# IMX7S_CPU_POWER.net
KiCad netlist of a schematic drawn in Altium Designer
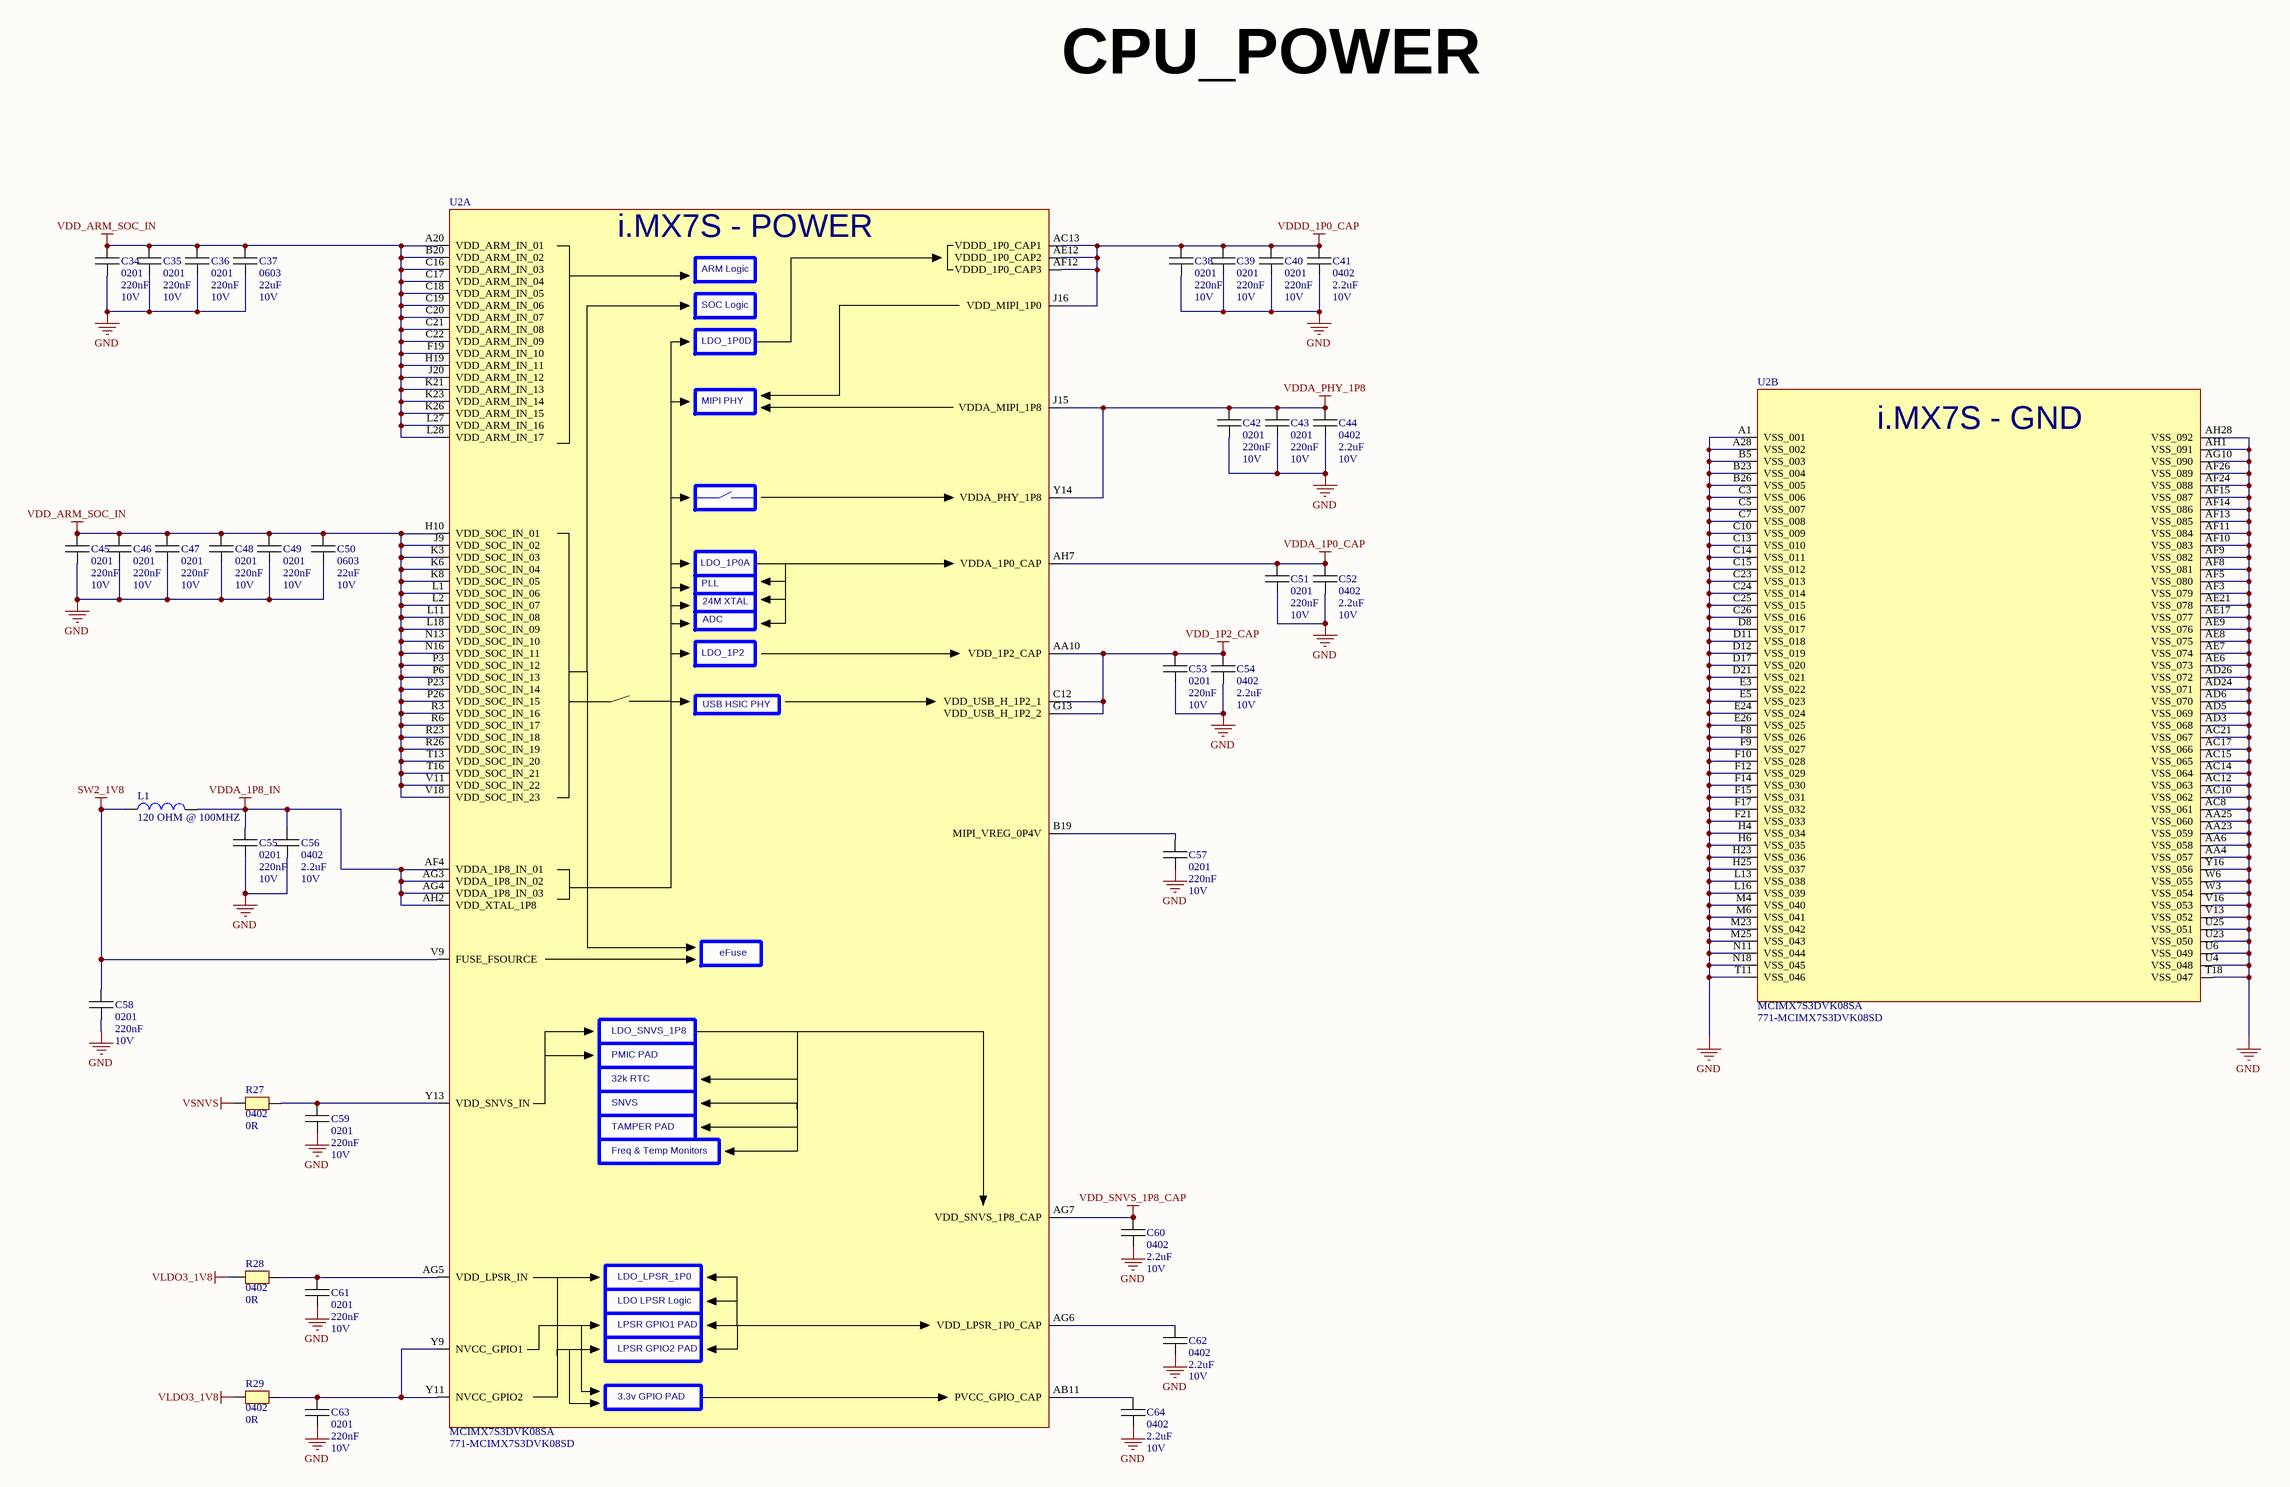
[diagram p0: IMX7S_CPU_POWER.SchDoc]

(export (version "E")
  (design (tool "Eeschema 10.0.6"))
  (components
    (comp (ref "C34")
      (value "220nF")
      (footprint "C0201")
      (fields
        (field (name "PACKAGE") "0201")
        (field (name "VOLTAGE") "10V")
        (field (name "TOLERANCE") "10%")
        (field (name "Comment") "C0201")
      )
      (libsource (lib "Schlib_IMX7") (part "C0201"))
    )
    (comp (ref "C35")
      (value "220nF")
      (footprint "C0201")
      (fields
        (field (name "PACKAGE") "0201")
        (field (name "VOLTAGE") "10V")
        (field (name "TOLERANCE") "10%")
        (field (name "Comment") "C0201")
      )
      (libsource (lib "Schlib_IMX7") (part "C0201"))
    )
    (comp (ref "C36")
      (value "220nF")
      (footprint "C0201")
      (fields
        (field (name "PACKAGE") "0201")
        (field (name "VOLTAGE") "10V")
        (field (name "TOLERANCE") "10%")
        (field (name "Comment") "C0201")
      )
      (libsource (lib "Schlib_IMX7") (part "C0201"))
    )
    (comp (ref "C37")
      (value "22uF")
      (footprint "C0603")
      (description "Cap Ceramic 22uF 6.3V X5R 20% SMD 0603 85C Paper T/R")
      (fields
        (field (name "PACKAGE") "0603")
        (field (name "VOLTAGE") "10V")
        (field (name "TOLERANCE") "20%")
        (field (name "Comment") "C0603")
      )
      (libsource (lib "Schlib_IMX7") (part "C0603"))
    )
    (comp (ref "C38")
      (value "220nF")
      (footprint "C0201")
      (fields
        (field (name "PACKAGE") "0201")
        (field (name "VOLTAGE") "10V")
        (field (name "TOLERANCE") "10%")
        (field (name "Comment") "C0201")
      )
      (libsource (lib "Schlib_IMX7") (part "C0201"))
    )
    (comp (ref "C39")
      (value "220nF")
      (footprint "C0201")
      (fields
        (field (name "PACKAGE") "0201")
        (field (name "VOLTAGE") "10V")
        (field (name "TOLERANCE") "10%")
        (field (name "Comment") "C0201")
      )
      (libsource (lib "Schlib_IMX7") (part "C0201"))
    )
    (comp (ref "C40")
      (value "220nF")
      (footprint "C0201")
      (fields
        (field (name "PACKAGE") "0201")
        (field (name "VOLTAGE") "10V")
        (field (name "TOLERANCE") "10%")
        (field (name "Comment") "C0201")
      )
      (libsource (lib "Schlib_IMX7") (part "C0201"))
    )
    (comp (ref "C41")
      (value "2.2uF")
      (footprint "C0402")
      (fields
        (field (name "PACKAGE") "0402")
        (field (name "VOLTAGE") "10V")
        (field (name "TOLERANCE") "20%")
        (field (name "Comment") "C0402")
      )
      (libsource (lib "Schlib_IMX7") (part "C0402"))
    )
    (comp (ref "C42")
      (value "220nF")
      (footprint "C0201")
      (fields
        (field (name "PACKAGE") "0201")
        (field (name "VOLTAGE") "10V")
        (field (name "TOLERANCE") "10%")
        (field (name "Comment") "C0201")
      )
      (libsource (lib "Schlib_IMX7") (part "C0201"))
    )
    (comp (ref "C43")
      (value "220nF")
      (footprint "C0201")
      (fields
        (field (name "PACKAGE") "0201")
        (field (name "VOLTAGE") "10V")
        (field (name "TOLERANCE") "10%")
        (field (name "Comment") "C0201")
      )
      (libsource (lib "Schlib_IMX7") (part "C0201"))
    )
    (comp (ref "C44")
      (value "2.2uF")
      (footprint "C0402")
      (fields
        (field (name "PACKAGE") "0402")
        (field (name "VOLTAGE") "10V")
        (field (name "TOLERANCE") "20%")
        (field (name "Comment") "C0402")
      )
      (libsource (lib "Schlib_IMX7") (part "C0402"))
    )
    (comp (ref "C45")
      (value "220nF")
      (footprint "C0201")
      (fields
        (field (name "PACKAGE") "0201")
        (field (name "VOLTAGE") "10V")
        (field (name "TOLERANCE") "10%")
        (field (name "Comment") "C0201")
      )
      (libsource (lib "Schlib_IMX7") (part "C0201"))
    )
    (comp (ref "C46")
      (value "220nF")
      (footprint "C0201")
      (fields
        (field (name "PACKAGE") "0201")
        (field (name "VOLTAGE") "10V")
        (field (name "TOLERANCE") "10%")
        (field (name "Comment") "C0201")
      )
      (libsource (lib "Schlib_IMX7") (part "C0201"))
    )
    (comp (ref "C47")
      (value "220nF")
      (footprint "C0201")
      (fields
        (field (name "PACKAGE") "0201")
        (field (name "VOLTAGE") "10V")
        (field (name "TOLERANCE") "10%")
        (field (name "Comment") "C0201")
      )
      (libsource (lib "Schlib_IMX7") (part "C0201"))
    )
    (comp (ref "C48")
      (value "220nF")
      (footprint "C0201")
      (fields
        (field (name "PACKAGE") "0201")
        (field (name "VOLTAGE") "10V")
        (field (name "TOLERANCE") "10%")
        (field (name "Comment") "C0201")
      )
      (libsource (lib "Schlib_IMX7") (part "C0201"))
    )
    (comp (ref "C49")
      (value "220nF")
      (footprint "C0201")
      (fields
        (field (name "PACKAGE") "0201")
        (field (name "VOLTAGE") "10V")
        (field (name "TOLERANCE") "10%")
        (field (name "Comment") "C0201")
      )
      (libsource (lib "Schlib_IMX7") (part "C0201"))
    )
    (comp (ref "C50")
      (value "22uF")
      (footprint "C0603")
      (description "Cap Ceramic 22uF 6.3V X5R 20% SMD 0603 85C Paper T/R")
      (fields
        (field (name "PACKAGE") "0603")
        (field (name "VOLTAGE") "10V")
        (field (name "TOLERANCE") "20%")
        (field (name "Comment") "C0603")
      )
      (libsource (lib "Schlib_IMX7") (part "C0603"))
    )
    (comp (ref "C51")
      (value "220nF")
      (footprint "C0201")
      (fields
        (field (name "PACKAGE") "0201")
        (field (name "VOLTAGE") "10V")
        (field (name "TOLERANCE") "10%")
        (field (name "Comment") "C0201")
      )
      (libsource (lib "Schlib_IMX7") (part "C0201"))
    )
    (comp (ref "C52")
      (value "2.2uF")
      (footprint "C0402")
      (fields
        (field (name "PACKAGE") "0402")
        (field (name "VOLTAGE") "10V")
        (field (name "TOLERANCE") "20%")
        (field (name "Comment") "C0402")
      )
      (libsource (lib "Schlib_IMX7") (part "C0402"))
    )
    (comp (ref "C53")
      (value "220nF")
      (footprint "C0201")
      (fields
        (field (name "PACKAGE") "0201")
        (field (name "VOLTAGE") "10V")
        (field (name "TOLERANCE") "10%")
        (field (name "Comment") "C0201")
      )
      (libsource (lib "Schlib_IMX7") (part "C0201"))
    )
    (comp (ref "C54")
      (value "2.2uF")
      (footprint "C0402")
      (fields
        (field (name "PACKAGE") "0402")
        (field (name "VOLTAGE") "10V")
        (field (name "TOLERANCE") "20%")
        (field (name "Comment") "C0402")
      )
      (libsource (lib "Schlib_IMX7") (part "C0402"))
    )
    (comp (ref "C55")
      (value "220nF")
      (footprint "C0201")
      (fields
        (field (name "PACKAGE") "0201")
        (field (name "VOLTAGE") "10V")
        (field (name "TOLERANCE") "10%")
        (field (name "Comment") "C0201")
      )
      (libsource (lib "Schlib_IMX7") (part "C0201"))
    )
    (comp (ref "C56")
      (value "2.2uF")
      (footprint "C0402")
      (fields
        (field (name "PACKAGE") "0402")
        (field (name "VOLTAGE") "10V")
        (field (name "TOLERANCE") "20%")
        (field (name "Comment") "C0402")
      )
      (libsource (lib "Schlib_IMX7") (part "C0402"))
    )
    (comp (ref "C57")
      (value "220nF")
      (footprint "C0201")
      (fields
        (field (name "PACKAGE") "0201")
        (field (name "VOLTAGE") "10V")
        (field (name "TOLERANCE") "10%")
        (field (name "Comment") "C0201")
      )
      (libsource (lib "Schlib_IMX7") (part "C0201"))
    )
    (comp (ref "C58")
      (value "220nF")
      (footprint "C0201")
      (fields
        (field (name "PACKAGE") "0201")
        (field (name "VOLTAGE") "10V")
        (field (name "TOLERANCE") "10%")
        (field (name "Comment") "C0201")
      )
      (libsource (lib "Schlib_IMX7") (part "C0201"))
    )
    (comp (ref "C59")
      (value "220nF")
      (footprint "C0201")
      (fields
        (field (name "PACKAGE") "0201")
        (field (name "VOLTAGE") "10V")
        (field (name "TOLERANCE") "10%")
        (field (name "Comment") "C0201")
      )
      (libsource (lib "Schlib_IMX7") (part "C0201"))
    )
    (comp (ref "C60")
      (value "2.2uF")
      (footprint "C0402")
      (fields
        (field (name "PACKAGE") "0402")
        (field (name "VOLTAGE") "10V")
        (field (name "TOLERANCE") "20%")
        (field (name "Comment") "C0402")
      )
      (libsource (lib "Schlib_IMX7") (part "C0402"))
    )
    (comp (ref "C61")
      (value "220nF")
      (footprint "C0201")
      (fields
        (field (name "PACKAGE") "0201")
        (field (name "VOLTAGE") "10V")
        (field (name "TOLERANCE") "10%")
        (field (name "Comment") "C0201")
      )
      (libsource (lib "Schlib_IMX7") (part "C0201"))
    )
    (comp (ref "C62")
      (value "2.2uF")
      (footprint "C0402")
      (fields
        (field (name "PACKAGE") "0402")
        (field (name "VOLTAGE") "10V")
        (field (name "TOLERANCE") "20%")
        (field (name "Comment") "C0402")
      )
      (libsource (lib "Schlib_IMX7") (part "C0402"))
    )
    (comp (ref "C63")
      (value "220nF")
      (footprint "C0201")
      (fields
        (field (name "PACKAGE") "0201")
        (field (name "VOLTAGE") "10V")
        (field (name "TOLERANCE") "10%")
        (field (name "Comment") "C0201")
      )
      (libsource (lib "Schlib_IMX7") (part "C0201"))
    )
    (comp (ref "C64")
      (value "2.2uF")
      (footprint "C0402")
      (fields
        (field (name "PACKAGE") "0402")
        (field (name "VOLTAGE") "10V")
        (field (name "TOLERANCE") "20%")
        (field (name "Comment") "C0402")
      )
      (libsource (lib "Schlib_IMX7") (part "C0402"))
    )
    (comp (ref "L1")
      (value "120 OHM @ 100MHZ")
      (footprint "SELF")
      (description "10mH Unshielded Wirewound Inductor 35mA 120 Ohm Max 2220 (5750 Metric)")
      (fields (field (name "TOLERANCE") "10%") (field (name "Comment") "Self"))
      (libsource (lib "Schlib_IMX7") (part "Self"))
    )
    (comp (ref "R27")
      (value "0R")
      (footprint "R0402")
      (description "MULTICOMP - MCSR04X000 PTL - RES, 0R0, 0.0625W, 0402, CERAMIC")
      (fields (field (name "PACKAGE") "0402") (field (name "VOLTAGE") "0V") (field (name "Comment") "R0402"))
      (libsource (lib "Schlib_IMX7") (part "R0402"))
    )
    (comp (ref "R28")
      (value "0R")
      (footprint "R0402")
      (description "MULTICOMP - MCSR04X000 PTL - RES, 0R0, 0.0625W, 0402, CERAMIC")
      (fields (field (name "PACKAGE") "0402") (field (name "VOLTAGE") "0V") (field (name "Comment") "R0402"))
      (libsource (lib "Schlib_IMX7") (part "R0402"))
    )
    (comp (ref "R29")
      (value "0R")
      (footprint "R0402")
      (description "MULTICOMP - MCSR04X000 PTL - RES, 0R0, 0.0625W, 0402, CERAMIC")
      (fields (field (name "PACKAGE") "0402") (field (name "VOLTAGE") "0V") (field (name "Comment") "R0402"))
      (libsource (lib "Schlib_IMX7") (part "R0402"))
    )
    (comp (ref "U2")
      (value "MCIMX7S3DVK08SA")
      (footprint "BGA 488 PIN")
      (fields (field (name "SUPPLIER PART NUMBER 1") "771-MCIMX7S3DVK08SD"))
      (libsource (lib "Schlib_IMX7") (part "MCIMX7S3DVK08SD"))
    )
  )
  (nets
    (net (code "1") (name "GND") (class "Default")
      (node (ref "C34") (pin "1") (pinfunction "1_1") (pintype "passive"))
      (node (ref "C35") (pin "1") (pinfunction "1_1") (pintype "passive"))
      (node (ref "C36") (pin "1") (pinfunction "1_1") (pintype "passive"))
      (node (ref "C37") (pin "1") (pinfunction "1_1") (pintype "passive"))
      (node (ref "C38") (pin "1") (pinfunction "1_1") (pintype "passive"))
      (node (ref "C39") (pin "1") (pinfunction "1_1") (pintype "passive"))
      (node (ref "C40") (pin "1") (pinfunction "1_1") (pintype "passive"))
      (node (ref "C41") (pin "1") (pinfunction "1_1") (pintype "passive"))
      (node (ref "C42") (pin "1") (pinfunction "1_1") (pintype "passive"))
      (node (ref "C43") (pin "1") (pinfunction "1_1") (pintype "passive"))
      (node (ref "C44") (pin "1") (pinfunction "1_1") (pintype "passive"))
      (node (ref "C45") (pin "1") (pinfunction "1_1") (pintype "passive"))
      (node (ref "C46") (pin "1") (pinfunction "1_1") (pintype "passive"))
      (node (ref "C47") (pin "1") (pinfunction "1_1") (pintype "passive"))
      (node (ref "C48") (pin "1") (pinfunction "1_1") (pintype "passive"))
      (node (ref "C49") (pin "1") (pinfunction "1_1") (pintype "passive"))
      (node (ref "C50") (pin "1") (pinfunction "1_1") (pintype "passive"))
      (node (ref "C51") (pin "1") (pinfunction "1_1") (pintype "passive"))
      (node (ref "C52") (pin "1") (pinfunction "1_1") (pintype "passive"))
      (node (ref "C53") (pin "1") (pinfunction "1_1") (pintype "passive"))
      (node (ref "C54") (pin "1") (pinfunction "1_1") (pintype "passive"))
      (node (ref "C55") (pin "1") (pinfunction "1_1") (pintype "passive"))
      (node (ref "C56") (pin "1") (pinfunction "1_1") (pintype "passive"))
      (node (ref "C57") (pin "1") (pinfunction "1_1") (pintype "passive"))
      (node (ref "C58") (pin "1") (pinfunction "1_1") (pintype "passive"))
      (node (ref "C59") (pin "1") (pinfunction "1_1") (pintype "passive"))
      (node (ref "C60") (pin "1") (pinfunction "1_1") (pintype "passive"))
      (node (ref "C61") (pin "1") (pinfunction "1_1") (pintype "passive"))
      (node (ref "C62") (pin "1") (pinfunction "1_1") (pintype "passive"))
      (node (ref "C63") (pin "1") (pinfunction "1_1") (pintype "passive"))
      (node (ref "C64") (pin "1") (pinfunction "1_1") (pintype "passive"))
      (node (ref "U2") (pin "A1") (pinfunction "VSS_001_A1") (pintype "passive"))
      (node (ref "U2") (pin "A28") (pinfunction "VSS_002_A28") (pintype "passive"))
      (node (ref "U2") (pin "AA23") (pinfunction "VSS_059_AA23") (pintype "passive"))
      (node (ref "U2") (pin "AA25") (pinfunction "VSS_060_AA25") (pintype "passive"))
      (node (ref "U2") (pin "AA4") (pinfunction "VSS_057_AA4") (pintype "passive"))
      (node (ref "U2") (pin "AA6") (pinfunction "VSS_058_AA6") (pintype "passive"))
      (node (ref "U2") (pin "AC10") (pinfunction "VSS_062_AC10") (pintype "passive"))
      (node (ref "U2") (pin "AC12") (pinfunction "VSS_063_AC12") (pintype "passive"))
      (node (ref "U2") (pin "AC14") (pinfunction "VSS_064_AC14") (pintype "passive"))
      (node (ref "U2") (pin "AC15") (pinfunction "VSS_065_AC15") (pintype "passive"))
      (node (ref "U2") (pin "AC17") (pinfunction "VSS_066_AC17") (pintype "passive"))
      (node (ref "U2") (pin "AC21") (pinfunction "VSS_067_AC21") (pintype "passive"))
      (node (ref "U2") (pin "AC8") (pinfunction "VSS_061_AC8") (pintype "passive"))
      (node (ref "U2") (pin "AD24") (pinfunction "VSS_071_AD24") (pintype "passive"))
      (node (ref "U2") (pin "AD26") (pinfunction "VSS_072_AD26") (pintype "passive"))
      (node (ref "U2") (pin "AD3") (pinfunction "VSS_068_AD3") (pintype "passive"))
      (node (ref "U2") (pin "AD5") (pinfunction "VSS_069_AD5") (pintype "passive"))
      (node (ref "U2") (pin "AD6") (pinfunction "VSS_070_AD6") (pintype "passive"))
      (node (ref "U2") (pin "AE17") (pinfunction "VSS_077_AE17") (pintype "passive"))
      (node (ref "U2") (pin "AE21") (pinfunction "VSS_078_AE21") (pintype "passive"))
      (node (ref "U2") (pin "AE6") (pinfunction "VSS_073_AE6") (pintype "passive"))
      (node (ref "U2") (pin "AE7") (pinfunction "VSS_074_AE7") (pintype "passive"))
      (node (ref "U2") (pin "AE8") (pinfunction "VSS_075_AE8") (pintype "passive"))
      (node (ref "U2") (pin "AE9") (pinfunction "VSS_076_AE9") (pintype "passive"))
      (node (ref "U2") (pin "AF10") (pinfunction "VSS_083_AF10") (pintype "passive"))
      (node (ref "U2") (pin "AF11") (pinfunction "VSS_084_AF11") (pintype "passive"))
      (node (ref "U2") (pin "AF13") (pinfunction "VSS_085_AF13") (pintype "passive"))
      (node (ref "U2") (pin "AF14") (pinfunction "VSS_086_AF14") (pintype "passive"))
      (node (ref "U2") (pin "AF15") (pinfunction "VSS_087_AF15") (pintype "passive"))
      (node (ref "U2") (pin "AF24") (pinfunction "VSS_088_AF24") (pintype "passive"))
      (node (ref "U2") (pin "AF26") (pinfunction "VSS_089_AF26") (pintype "passive"))
      (node (ref "U2") (pin "AF3") (pinfunction "VSS_079_AF3") (pintype "passive"))
      (node (ref "U2") (pin "AF5") (pinfunction "VSS_080_AF5") (pintype "passive"))
      (node (ref "U2") (pin "AF8") (pinfunction "VSS_081_AF8") (pintype "passive"))
      (node (ref "U2") (pin "AF9") (pinfunction "VSS_082_AF9") (pintype "passive"))
      (node (ref "U2") (pin "AG10") (pinfunction "VSS_090_AG10") (pintype "passive"))
      (node (ref "U2") (pin "AH1") (pinfunction "VSS_091_AH1") (pintype "passive"))
      (node (ref "U2") (pin "AH28") (pinfunction "VSS_092_AH28") (pintype "passive"))
      (node (ref "U2") (pin "B23") (pinfunction "VSS_004_B23") (pintype "passive"))
      (node (ref "U2") (pin "B26") (pinfunction "VSS_005_B26") (pintype "passive"))
      (node (ref "U2") (pin "B5") (pinfunction "VSS_003_B5") (pintype "passive"))
      (node (ref "U2") (pin "C10") (pinfunction "VSS_009_C10") (pintype "passive"))
      (node (ref "U2") (pin "C13") (pinfunction "VSS_010_C13") (pintype "passive"))
      (node (ref "U2") (pin "C14") (pinfunction "VSS_011_C14") (pintype "passive"))
      (node (ref "U2") (pin "C15") (pinfunction "VSS_012_C15") (pintype "passive"))
      (node (ref "U2") (pin "C23") (pinfunction "VSS_013_C23") (pintype "passive"))
      (node (ref "U2") (pin "C24") (pinfunction "VSS_014_C24") (pintype "passive"))
      (node (ref "U2") (pin "C25") (pinfunction "VSS_015_C25") (pintype "passive"))
      (node (ref "U2") (pin "C26") (pinfunction "VSS_016_C26") (pintype "passive"))
      (node (ref "U2") (pin "C3") (pinfunction "VSS_006_C3") (pintype "passive"))
      (node (ref "U2") (pin "C5") (pinfunction "VSS_007_C5") (pintype "passive"))
      (node (ref "U2") (pin "C7") (pinfunction "VSS_008_C7") (pintype "passive"))
      (node (ref "U2") (pin "D11") (pinfunction "VSS_018_D11") (pintype "passive"))
      (node (ref "U2") (pin "D12") (pinfunction "VSS_019_D12") (pintype "passive"))
      (node (ref "U2") (pin "D17") (pinfunction "VSS_020_D17") (pintype "passive"))
      (node (ref "U2") (pin "D21") (pinfunction "VSS_021_D21") (pintype "passive"))
      (node (ref "U2") (pin "D8") (pinfunction "VSS_017_D8") (pintype "passive"))
      (node (ref "U2") (pin "E24") (pinfunction "VSS_024_E24") (pintype "passive"))
      (node (ref "U2") (pin "E26") (pinfunction "VSS_025_E26") (pintype "passive"))
      (node (ref "U2") (pin "E3") (pinfunction "VSS_022_E3") (pintype "passive"))
      (node (ref "U2") (pin "E5") (pinfunction "VSS_023_E5") (pintype "passive"))
      (node (ref "U2") (pin "F10") (pinfunction "VSS_028_F10") (pintype "passive"))
      (node (ref "U2") (pin "F12") (pinfunction "VSS_029_F12") (pintype "passive"))
      (node (ref "U2") (pin "F14") (pinfunction "VSS_030_F14") (pintype "passive"))
      (node (ref "U2") (pin "F15") (pinfunction "VSS_031_F15") (pintype "passive"))
      (node (ref "U2") (pin "F17") (pinfunction "VSS_032_F17") (pintype "passive"))
      (node (ref "U2") (pin "F21") (pinfunction "VSS_033_F21") (pintype "passive"))
      (node (ref "U2") (pin "F8") (pinfunction "VSS_026_F8") (pintype "passive"))
      (node (ref "U2") (pin "F9") (pinfunction "VSS_027_F9") (pintype "passive"))
      (node (ref "U2") (pin "H23") (pinfunction "VSS_036_H23") (pintype "passive"))
      (node (ref "U2") (pin "H25") (pinfunction "VSS_037_H25") (pintype "passive"))
      (node (ref "U2") (pin "H4") (pinfunction "VSS_034_H4") (pintype "passive"))
      (node (ref "U2") (pin "H6") (pinfunction "VSS_035_H6") (pintype "passive"))
      (node (ref "U2") (pin "L13") (pinfunction "VSS_038_L13") (pintype "passive"))
      (node (ref "U2") (pin "L16") (pinfunction "VSS_039_L16") (pintype "passive"))
      (node (ref "U2") (pin "M23") (pinfunction "VSS_042_M23") (pintype "passive"))
      (node (ref "U2") (pin "M25") (pinfunction "VSS_043_M25") (pintype "passive"))
      (node (ref "U2") (pin "M4") (pinfunction "VSS_040_M4") (pintype "passive"))
      (node (ref "U2") (pin "M6") (pinfunction "VSS_041_M6") (pintype "passive"))
      (node (ref "U2") (pin "N11") (pinfunction "VSS_044_N11") (pintype "passive"))
      (node (ref "U2") (pin "N18") (pinfunction "VSS_045_N18") (pintype "passive"))
      (node (ref "U2") (pin "T11") (pinfunction "VSS_046_T11") (pintype "passive"))
      (node (ref "U2") (pin "T18") (pinfunction "VSS_047_T18") (pintype "passive"))
      (node (ref "U2") (pin "U23") (pinfunction "VSS_050_U23") (pintype "passive"))
      (node (ref "U2") (pin "U25") (pinfunction "VSS_051_U25") (pintype "passive"))
      (node (ref "U2") (pin "U4") (pinfunction "VSS_048_U4") (pintype "passive"))
      (node (ref "U2") (pin "U6") (pinfunction "VSS_049_U6") (pintype "passive"))
      (node (ref "U2") (pin "V13") (pinfunction "VSS_052_V13") (pintype "passive"))
      (node (ref "U2") (pin "V16") (pinfunction "VSS_053_V16") (pintype "passive"))
      (node (ref "U2") (pin "W3") (pinfunction "VSS_054_W3") (pintype "passive"))
      (node (ref "U2") (pin "W6") (pinfunction "VSS_055_W6") (pintype "passive"))
      (node (ref "U2") (pin "Y16") (pinfunction "VSS_056_Y16") (pintype "passive"))
    )
    (net (code "2") (name "Net-(U2A-MIPI_VREG_0P4V)") (class "Default")
      (node (ref "C57") (pin "2") (pinfunction "2_2") (pintype "passive"))
      (node (ref "U2") (pin "B19") (pinfunction "MIPI_VREG_0P4V_B19") (pintype "passive"))
    )
    (net (code "3") (name "Net-(U2A-NVCC_GPIO1)") (class "Default")
      (node (ref "C63") (pin "2") (pinfunction "2_2") (pintype "passive"))
      (node (ref "R29") (pin "2") (pinfunction "2_2") (pintype "passive"))
      (node (ref "U2") (pin "Y11") (pinfunction "NVCC_GPIO2_Y11") (pintype "passive"))
      (node (ref "U2") (pin "Y9") (pinfunction "NVCC_GPIO1_Y9") (pintype "passive"))
    )
    (net (code "4") (name "Net-(U2A-PVCC_GPIO_CAP)") (class "Default")
      (node (ref "C64") (pin "2") (pinfunction "2_2") (pintype "passive"))
      (node (ref "U2") (pin "AB11") (pinfunction "PVCC_GPIO_CAP_AB11") (pintype "passive"))
    )
    (net (code "5") (name "Net-(U2A-VDD_LPSR_1P0_CAP)") (class "Default")
      (node (ref "C62") (pin "2") (pinfunction "2_2") (pintype "passive"))
      (node (ref "U2") (pin "AG6") (pinfunction "VDD_LPSR_1P0_CAP_AG6") (pintype "passive"))
    )
    (net (code "6") (name "Net-(U2A-VDD_LPSR_IN)") (class "Default")
      (node (ref "C61") (pin "2") (pinfunction "2_2") (pintype "passive"))
      (node (ref "R28") (pin "2") (pinfunction "2_2") (pintype "passive"))
      (node (ref "U2") (pin "AG5") (pinfunction "VDD_LPSR_IN_AG5") (pintype "passive"))
    )
    (net (code "7") (name "Net-(U2A-VDD_SNVS_IN)") (class "Default")
      (node (ref "C59") (pin "2") (pinfunction "2_2") (pintype "passive"))
      (node (ref "R27") (pin "2") (pinfunction "2_2") (pintype "passive"))
      (node (ref "U2") (pin "Y13") (pinfunction "VDD_SNVS_IN_Y13") (pintype "passive"))
    )
    (net (code "8") (name "SW2_1V8") (class "Default")
      (node (ref "C58") (pin "2") (pinfunction "2_2") (pintype "passive"))
      (node (ref "L1") (pin "1") (pintype "passive"))
      (node (ref "U2") (pin "V9") (pinfunction "FUSE_FSOURCE_V9") (pintype "passive"))
    )
    (net (code "9") (name "VDDA_1P0_CAP") (class "Default")
      (node (ref "C51") (pin "2") (pinfunction "2_2") (pintype "passive"))
      (node (ref "C52") (pin "2") (pinfunction "2_2") (pintype "passive"))
      (node (ref "U2") (pin "AH7") (pinfunction "VDDA_1P0_CAP_AH7") (pintype "passive"))
    )
    (net (code "10") (name "VDDA_1P8_IN") (class "Default")
      (node (ref "C55") (pin "2") (pinfunction "2_2") (pintype "passive"))
      (node (ref "C56") (pin "2") (pinfunction "2_2") (pintype "passive"))
      (node (ref "L1") (pin "2") (pintype "passive"))
      (node (ref "U2") (pin "AF4") (pinfunction "VDDA_1P8_IN_01_AF4") (pintype "passive"))
      (node (ref "U2") (pin "AG3") (pinfunction "VDDA_1P8_IN_02_AG3") (pintype "passive"))
      (node (ref "U2") (pin "AG4") (pinfunction "VDDA_1P8_IN_03_AG4") (pintype "passive"))
      (node (ref "U2") (pin "AH2") (pinfunction "VDD_XTAL_1P8_AH2") (pintype "passive"))
    )
    (net (code "11") (name "VDDA_PHY_1P8") (class "Default")
      (node (ref "C42") (pin "2") (pinfunction "2_2") (pintype "passive"))
      (node (ref "C43") (pin "2") (pinfunction "2_2") (pintype "passive"))
      (node (ref "C44") (pin "2") (pinfunction "2_2") (pintype "passive"))
      (node (ref "U2") (pin "J15") (pinfunction "VDDA_MIPI_1P8_J15") (pintype "passive"))
      (node (ref "U2") (pin "Y14") (pinfunction "VDDA_PHY_1P8_Y14") (pintype "passive"))
    )
    (net (code "12") (name "VDDD_1P0_CAP") (class "Default")
      (node (ref "C38") (pin "2") (pinfunction "2_2") (pintype "passive"))
      (node (ref "C39") (pin "2") (pinfunction "2_2") (pintype "passive"))
      (node (ref "C40") (pin "2") (pinfunction "2_2") (pintype "passive"))
      (node (ref "C41") (pin "2") (pinfunction "2_2") (pintype "passive"))
      (node (ref "U2") (pin "AC13") (pinfunction "VDDD_1P0_CAP1_AC13") (pintype "passive"))
      (node (ref "U2") (pin "AE12") (pinfunction "VDDD_1P0_CAP2_AE12") (pintype "passive"))
      (node (ref "U2") (pin "AF12") (pinfunction "VDDD_1P0_CAP3_AF12") (pintype "passive"))
      (node (ref "U2") (pin "J16") (pinfunction "VDD_MIPI_1P0_J16") (pintype "passive"))
    )
    (net (code "13") (name "VDD_1P2_CAP") (class "Default")
      (node (ref "C53") (pin "2") (pinfunction "2_2") (pintype "passive"))
      (node (ref "C54") (pin "2") (pinfunction "2_2") (pintype "passive"))
      (node (ref "U2") (pin "AA10") (pinfunction "VDD_1P2_CAP_AA10") (pintype "passive"))
      (node (ref "U2") (pin "C12") (pinfunction "VDD_USB_H_1P2_1_C12") (pintype "passive"))
      (node (ref "U2") (pin "G13") (pinfunction "VDD_USB_H_1P2_2_G13") (pintype "passive"))
    )
    (net (code "14") (name "VDD_ARM_SOC_IN") (class "Default")
      (node (ref "C34") (pin "2") (pinfunction "2_2") (pintype "passive"))
      (node (ref "C35") (pin "2") (pinfunction "2_2") (pintype "passive"))
      (node (ref "C36") (pin "2") (pinfunction "2_2") (pintype "passive"))
      (node (ref "C37") (pin "2") (pinfunction "2_2") (pintype "passive"))
      (node (ref "C45") (pin "2") (pinfunction "2_2") (pintype "passive"))
      (node (ref "C46") (pin "2") (pinfunction "2_2") (pintype "passive"))
      (node (ref "C47") (pin "2") (pinfunction "2_2") (pintype "passive"))
      (node (ref "C48") (pin "2") (pinfunction "2_2") (pintype "passive"))
      (node (ref "C49") (pin "2") (pinfunction "2_2") (pintype "passive"))
      (node (ref "C50") (pin "2") (pinfunction "2_2") (pintype "passive"))
      (node (ref "U2") (pin "A20") (pinfunction "VDD_ARM_IN_01_A20") (pintype "passive"))
      (node (ref "U2") (pin "B20") (pinfunction "VDD_ARM_IN_02_B20") (pintype "passive"))
      (node (ref "U2") (pin "C16") (pinfunction "VDD_ARM_IN_03_C16") (pintype "passive"))
      (node (ref "U2") (pin "C17") (pinfunction "VDD_ARM_IN_04_C17") (pintype "passive"))
      (node (ref "U2") (pin "C18") (pinfunction "VDD_ARM_IN_05_C18") (pintype "passive"))
      (node (ref "U2") (pin "C19") (pinfunction "VDD_ARM_IN_06_C19") (pintype "passive"))
      (node (ref "U2") (pin "C20") (pinfunction "VDD_ARM_IN_07_C20") (pintype "passive"))
      (node (ref "U2") (pin "C21") (pinfunction "VDD_ARM_IN_08_C21") (pintype "passive"))
      (node (ref "U2") (pin "C22") (pinfunction "VDD_ARM_IN_09_C22") (pintype "passive"))
      (node (ref "U2") (pin "F19") (pinfunction "VDD_ARM_IN_10_F19") (pintype "passive"))
      (node (ref "U2") (pin "H10") (pinfunction "VDD_SOC_IN_01_H10") (pintype "passive"))
      (node (ref "U2") (pin "H19") (pinfunction "VDD_ARM_IN_11_H19") (pintype "passive"))
      (node (ref "U2") (pin "J20") (pinfunction "VDD_ARM_IN_12_J20") (pintype "passive"))
      (node (ref "U2") (pin "J9") (pinfunction "VDD_SOC_IN_02_J9") (pintype "passive"))
      (node (ref "U2") (pin "K21") (pinfunction "VDD_ARM_IN_13_K21") (pintype "passive"))
      (node (ref "U2") (pin "K23") (pinfunction "VDD_ARM_IN_14_K23") (pintype "passive"))
      (node (ref "U2") (pin "K26") (pinfunction "VDD_ARM_IN_15_K26") (pintype "passive"))
      (node (ref "U2") (pin "K3") (pinfunction "VDD_SOC_IN_03_K3") (pintype "passive"))
      (node (ref "U2") (pin "K6") (pinfunction "VDD_SOC_IN_04_K6") (pintype "passive"))
      (node (ref "U2") (pin "K8") (pinfunction "VDD_SOC_IN_05_K8") (pintype "passive"))
      (node (ref "U2") (pin "L1") (pinfunction "VDD_SOC_IN_06_L1") (pintype "passive"))
      (node (ref "U2") (pin "L11") (pinfunction "VDD_SOC_IN_08_L11") (pintype "passive"))
      (node (ref "U2") (pin "L18") (pinfunction "VDD_SOC_IN_09_L18") (pintype "passive"))
      (node (ref "U2") (pin "L2") (pinfunction "VDD_SOC_IN_07_L2") (pintype "passive"))
      (node (ref "U2") (pin "L27") (pinfunction "VDD_ARM_IN_16_L27") (pintype "passive"))
      (node (ref "U2") (pin "L28") (pinfunction "VDD_ARM_IN_17_L28") (pintype "passive"))
      (node (ref "U2") (pin "N13") (pinfunction "VDD_SOC_IN_10_N13") (pintype "passive"))
      (node (ref "U2") (pin "N16") (pinfunction "VDD_SOC_IN_11_N16") (pintype "passive"))
      (node (ref "U2") (pin "P23") (pinfunction "VDD_SOC_IN_14_P23") (pintype "passive"))
      (node (ref "U2") (pin "P26") (pinfunction "VDD_SOC_IN_15_P26") (pintype "passive"))
      (node (ref "U2") (pin "P3") (pinfunction "VDD_SOC_IN_12_P3") (pintype "passive"))
      (node (ref "U2") (pin "P6") (pinfunction "VDD_SOC_IN_13_P6") (pintype "passive"))
      (node (ref "U2") (pin "R23") (pinfunction "VDD_SOC_IN_18_R23") (pintype "passive"))
      (node (ref "U2") (pin "R26") (pinfunction "VDD_SOC_IN_19_R26") (pintype "passive"))
      (node (ref "U2") (pin "R3") (pinfunction "VDD_SOC_IN_16_R3") (pintype "passive"))
      (node (ref "U2") (pin "R6") (pinfunction "VDD_SOC_IN_17_R6") (pintype "passive"))
      (node (ref "U2") (pin "T13") (pinfunction "VDD_SOC_IN_20_T13") (pintype "passive"))
      (node (ref "U2") (pin "T16") (pinfunction "VDD_SOC_IN_21_T16") (pintype "passive"))
      (node (ref "U2") (pin "V11") (pinfunction "VDD_SOC_IN_22_V11") (pintype "passive"))
      (node (ref "U2") (pin "V18") (pinfunction "VDD_SOC_IN_23_V18") (pintype "passive"))
    )
    (net (code "15") (name "VDD_SNVS_1P8_CAP") (class "Default")
      (node (ref "C60") (pin "2") (pinfunction "2_2") (pintype "passive"))
      (node (ref "U2") (pin "AG7") (pinfunction "VDD_SNVS_1P8_CAP_AG7") (pintype "passive"))
    )
    (net (code "16") (name "VLDO3_1V8") (class "Default")
      (node (ref "R28") (pin "1") (pinfunction "1_1") (pintype "passive"))
      (node (ref "R29") (pin "1") (pinfunction "1_1") (pintype "passive"))
    )
    (net (code "17") (name "VSNVS") (class "Default")
      (node (ref "R27") (pin "1") (pinfunction "1_1") (pintype "passive"))
    )
  )
)
